# wiTEMP.net
KiCad netlist of a schematic drawn in EAGLE
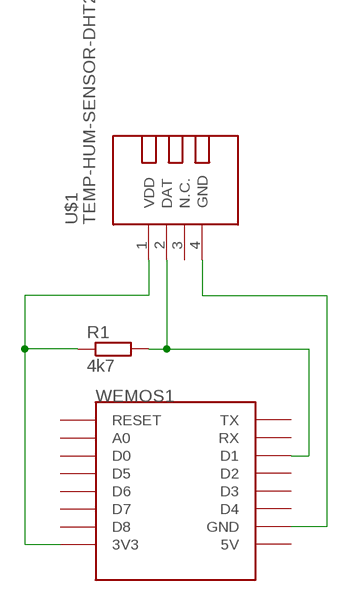
[diagram p0: schematic, sheet 1]

(export (version "E")
  (design (tool "Eeschema 10.0.6"))
  (components
    (comp (ref "R1")
      (value "4k7")
      (footprint "eagle-import:0207_10")
      (libsource (lib "eagle-import") (part "R-EU_0207/10"))
    )
    (comp (ref "U$1")
      (value "TEMP-HUM-SENSOR-DHT22")
      (footprint "eagle-import:TEMP-HUM-SENSOR-DHT22")
      (libsource (lib "eagle-import") (part "TEMP-HUM-SENSOR-DHT22"))
    )
    (comp (ref "WEMOS1")
      (value "WEMOS-D1-MINI")
      (footprint "eagle-import:WEMOS-D1-MINI")
      (libsource (lib "eagle-import") (part "WEMOS-D1-MINI"))
    )
  )
  (nets
    (net (code "1") (name "Net-(U$1-DAT)") (class "Default")
      (node (ref "R1") (pin "2") (pinfunction "2_2") (pintype "passive"))
      (node (ref "U$1") (pin "2") (pinfunction "DAT_2") (pintype "bidirectional"))
      (node (ref "WEMOS1") (pin "D1") (pinfunction "D1_D1") (pintype "bidirectional"))
    )
    (net (code "2") (name "Net-(U$1-GND)") (class "Default")
      (node (ref "U$1") (pin "4") (pinfunction "GND_4") (pintype "power_in"))
      (node (ref "WEMOS1") (pin "GND") (pinfunction "GND_GND") (pintype "bidirectional"))
    )
    (net (code "3") (name "Net-(U$1-VDD)") (class "Default")
      (node (ref "R1") (pin "1") (pinfunction "1_1") (pintype "passive"))
      (node (ref "U$1") (pin "1") (pinfunction "VDD_1") (pintype "power_in"))
      (node (ref "WEMOS1") (pin "3V3") (pinfunction "3V3_3V3") (pintype "bidirectional"))
    )
    (net (code "4") (name "unconnected-(U$1-N.C.-Pad3)") (class "Default")
      (node (ref "U$1") (pin "3") (pinfunction "N.C._3") (pintype "passive"))
    )
    (net (code "5") (name "unconnected-(WEMOS1-Pad5V)") (class "Default")
      (node (ref "WEMOS1") (pin "5V") (pinfunction "5V_5V") (pintype "bidirectional"))
    )
    (net (code "6") (name "unconnected-(WEMOS1-PadA0)") (class "Default")
      (node (ref "WEMOS1") (pin "A0") (pinfunction "A0_A0") (pintype "bidirectional"))
    )
    (net (code "7") (name "unconnected-(WEMOS1-PadD0)") (class "Default")
      (node (ref "WEMOS1") (pin "D0") (pinfunction "D0_D0") (pintype "bidirectional"))
    )
    (net (code "8") (name "unconnected-(WEMOS1-PadD2)") (class "Default")
      (node (ref "WEMOS1") (pin "D2") (pinfunction "D2_D2") (pintype "bidirectional"))
    )
    (net (code "9") (name "unconnected-(WEMOS1-PadD3)") (class "Default")
      (node (ref "WEMOS1") (pin "D3") (pinfunction "D3_D3") (pintype "bidirectional"))
    )
    (net (code "10") (name "unconnected-(WEMOS1-PadD4)") (class "Default")
      (node (ref "WEMOS1") (pin "D4") (pinfunction "D4_D4") (pintype "bidirectional"))
    )
    (net (code "11") (name "unconnected-(WEMOS1-PadD5)") (class "Default")
      (node (ref "WEMOS1") (pin "D5") (pinfunction "D5_D5") (pintype "bidirectional"))
    )
    (net (code "12") (name "unconnected-(WEMOS1-PadD6)") (class "Default")
      (node (ref "WEMOS1") (pin "D6") (pinfunction "D6_D6") (pintype "bidirectional"))
    )
    (net (code "13") (name "unconnected-(WEMOS1-PadD7)") (class "Default")
      (node (ref "WEMOS1") (pin "D7") (pinfunction "D7_D7") (pintype "bidirectional"))
    )
    (net (code "14") (name "unconnected-(WEMOS1-PadD8)") (class "Default")
      (node (ref "WEMOS1") (pin "D8") (pinfunction "D8_D8") (pintype "bidirectional"))
    )
    (net (code "15") (name "unconnected-(WEMOS1-PadRESET)") (class "Default")
      (node (ref "WEMOS1") (pin "RESET") (pinfunction "RESET_RESET") (pintype "bidirectional"))
    )
    (net (code "16") (name "unconnected-(WEMOS1-PadRX)") (class "Default")
      (node (ref "WEMOS1") (pin "RX") (pinfunction "RX_RX") (pintype "bidirectional"))
    )
    (net (code "17") (name "unconnected-(WEMOS1-PadTX)") (class "Default")
      (node (ref "WEMOS1") (pin "TX") (pinfunction "TX_TX") (pintype "bidirectional"))
    )
  )
)
